# MAXREFDES117.net
KiCad netlist of a schematic drawn in Altium Designer
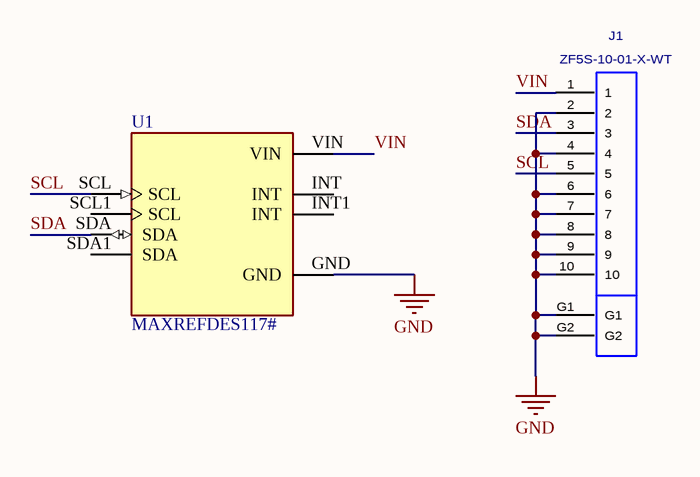
[diagram p0: MAXREFDES117.SchDoc]

(export (version "E")
  (design (tool "Eeschema 10.0.6"))
  (components
    (comp (ref "J1")
      (value "ZF5S-10-01-X-WT")
      (footprint "ZF5S-10-01-X-WT")
      (description "ZERO INSERTION FORCE 0.5MM ASSEMBLY, 01 LEAD STYLE.")
      (fields (field (name "MANUFACTURER") "SAMTEC") (field (name "CREATED") "January 30, 2015 - Wendy Xin"))
      (libsource (lib "ZF5S-10-01-X-WT--Symbol-Altium-44987") (part "ZF5S-10-01-X-WT"))
    )
    (comp (ref "U1")
      (value "MAXREFDES117#")
      (footprint "MODULE_MAXREFDES117#")
      (description "MAX1921, MAX14595, MAX30102 - Medical, Pulse Oximeter (PO or SpO2) Sensor Evaluation Board")
      (fields (field (name "MF") "Maxim Integrated"))
      (libsource (lib "MAXREFDES117_") (part "MAXREFDES117#"))
    )
  )
  (nets
    (net (code "1") (name "/SCL") (class "Default")
      (node (ref "J1") (pin "5") (pinfunction "5_5") (pintype "passive"))
      (node (ref "U1") (pin "SCL") (pinfunction "SCL_SCL") (pintype "input"))
    )
    (net (code "2") (name "/SDA") (class "Default")
      (node (ref "J1") (pin "3") (pinfunction "3_3") (pintype "passive"))
      (node (ref "U1") (pin "SDA") (pinfunction "SDA_SDA") (pintype "bidirectional"))
    )
    (net (code "3") (name "/VIN") (class "Default")
      (node (ref "J1") (pin "1") (pinfunction "1_1") (pintype "passive"))
      (node (ref "U1") (pin "VIN") (pinfunction "VIN_VIN") (pintype "power_in"))
    )
    (net (code "4") (name "GND") (class "Default")
      (node (ref "J1") (pin "10") (pinfunction "10_10") (pintype "passive"))
      (node (ref "J1") (pin "2") (pinfunction "2_2") (pintype "passive"))
      (node (ref "J1") (pin "4") (pinfunction "4_4") (pintype "passive"))
      (node (ref "J1") (pin "6") (pinfunction "6_6") (pintype "passive"))
      (node (ref "J1") (pin "7") (pinfunction "7_7") (pintype "passive"))
      (node (ref "J1") (pin "8") (pinfunction "8_8") (pintype "passive"))
      (node (ref "J1") (pin "9") (pinfunction "9_9") (pintype "passive"))
      (node (ref "J1") (pin "G1") (pinfunction "G1_G1") (pintype "passive"))
      (node (ref "J1") (pin "G2") (pinfunction "G2_G2") (pintype "passive"))
      (node (ref "U1") (pin "GND") (pinfunction "GND_GND") (pintype "power_in"))
    )
    (net (code "5") (name "unconnected-(U1-INT-PadINT1)") (class "Default")
      (node (ref "U1") (pin "INT1") (pinfunction "INT_INT1") (pintype "passive"))
    )
    (net (code "6") (name "unconnected-(U1-PadINT)") (class "Default")
      (node (ref "U1") (pin "INT") (pinfunction "INT_INT") (pintype "passive"))
    )
    (net (code "7") (name "unconnected-(U1-SCL-PadSCL1)") (class "Default")
      (node (ref "U1") (pin "SCL1") (pinfunction "SCL_SCL1") (pintype "passive"))
    )
    (net (code "8") (name "unconnected-(U1-SDA-PadSDA1)") (class "Default")
      (node (ref "U1") (pin "SDA1") (pinfunction "SDA_SDA1") (pintype "passive"))
    )
  )
)
